# crown-layout.net
KiCad netlist of a schematic drawn in EAGLE
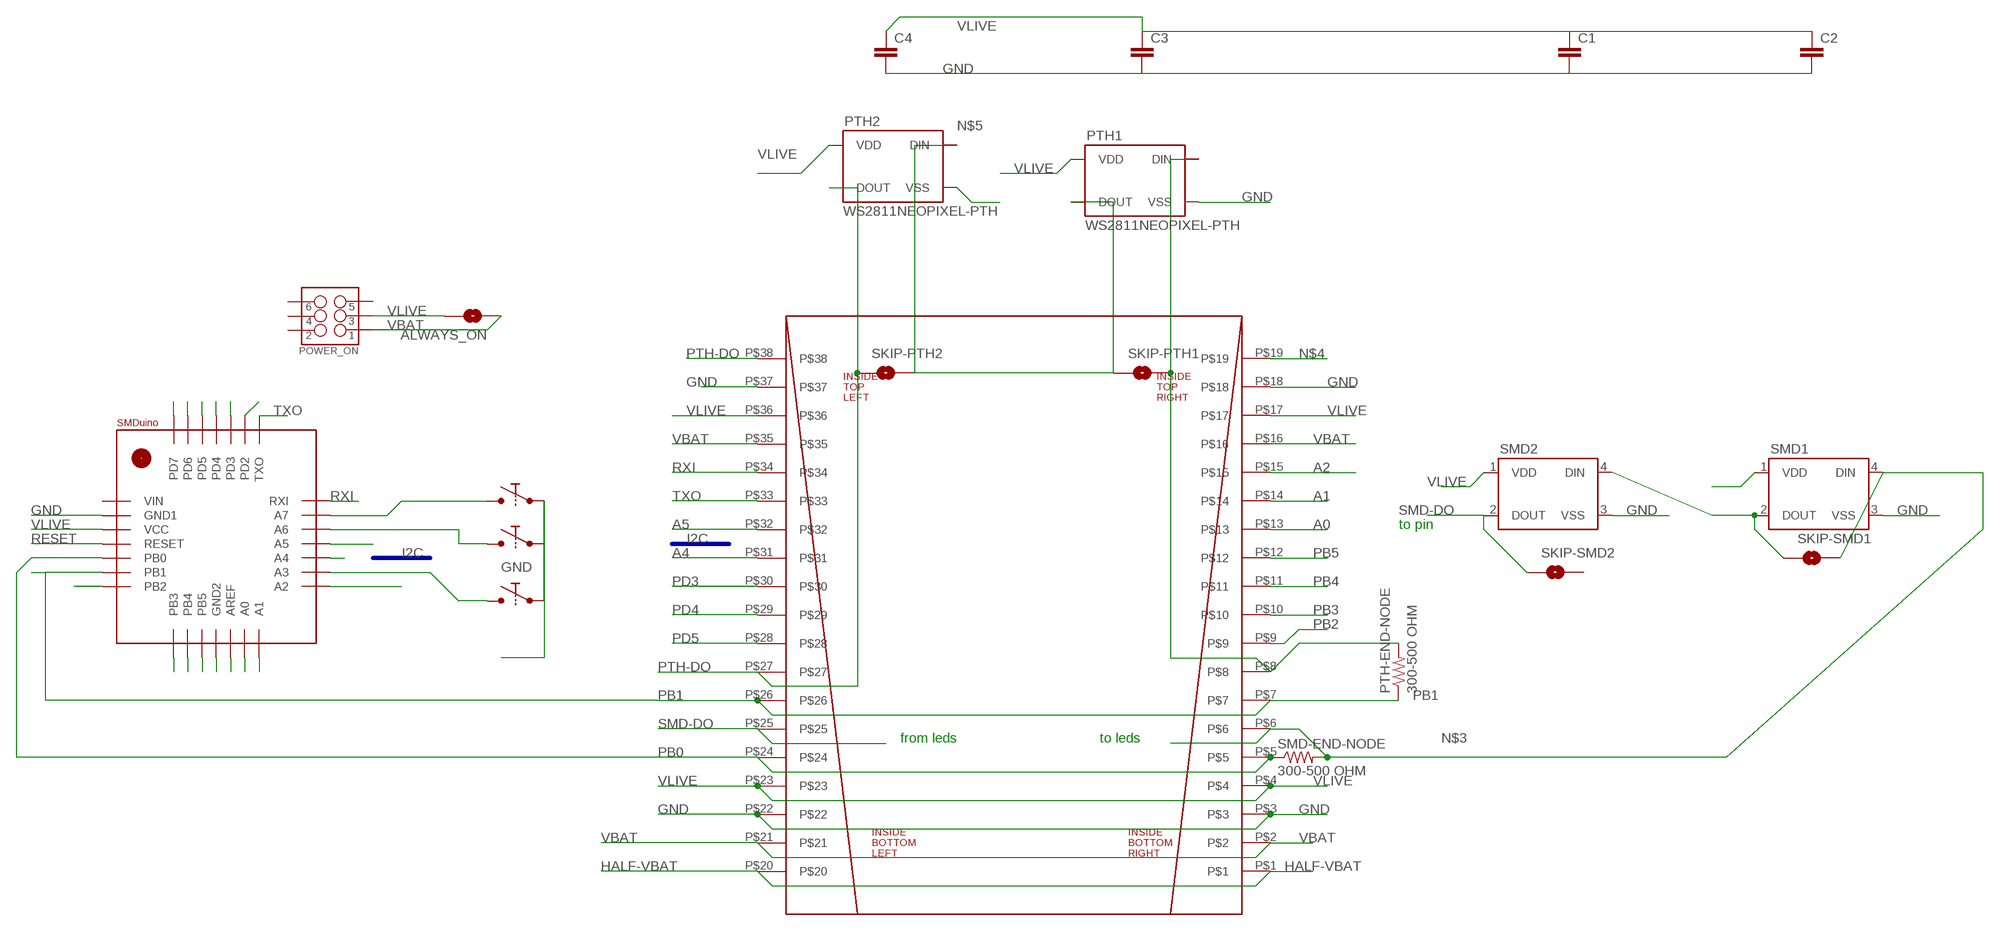
[diagram p0: schematic, sheet 1]

(export (version "E")
  (design (tool "Eeschema 10.0.6"))
  (components
    (comp (ref "A6")
      (value "BUTTONSMD_BUTTON")
      (footprint "eagle-import:SMD_BUTTON")
      (libsource (lib "eagle-import") (part "BUTTONSMD_BUTTON"))
    )
    (comp (ref "A7")
      (value "BUTTONSMD_BUTTON")
      (footprint "eagle-import:SMD_BUTTON")
      (libsource (lib "eagle-import") (part "BUTTONSMD_BUTTON"))
    )
    (comp (ref "ALWAYS_ON")
      (value "SOLDERJUMPERNC2")
      (footprint "eagle-import:SJ_2S-NOTRACE")
      (libsource (lib "eagle-import") (part "SOLDERJUMPERNC2"))
    )
    (comp (ref "C1")
      (value "CAP0805")
      (footprint "eagle-import:0805")
      (libsource (lib "eagle-import") (part "CAP0805"))
    )
    (comp (ref "C2")
      (value "CAP0805")
      (footprint "eagle-import:0805")
      (libsource (lib "eagle-import") (part "CAP0805"))
    )
    (comp (ref "C3")
      (value "CAP0805")
      (footprint "eagle-import:0805")
      (libsource (lib "eagle-import") (part "CAP0805"))
    )
    (comp (ref "C4")
      (value "CAP0805")
      (footprint "eagle-import:0805")
      (libsource (lib "eagle-import") (part "CAP0805"))
    )
    (comp (ref "D2")
      (value "BUTTONSMD_BUTTON")
      (footprint "eagle-import:SMD_BUTTON")
      (libsource (lib "eagle-import") (part "BUTTONSMD_BUTTON"))
    )
    (comp (ref "POWER_ON")
      (value "M03X2FEMALE_SMD")
      (footprint "eagle-import:2X3_SMD")
      (libsource (lib "eagle-import") (part "M03X2FEMALE_SMD"))
    )
    (comp (ref "PTH-END-NODE")
      (value "300-500 OHM")
      (footprint "eagle-import:0805")
      (libsource (lib "eagle-import") (part "RESISTOR0805-RES"))
    )
    (comp (ref "PTH1")
      (value "WS2811NEOPIXEL-PTH")
      (footprint "eagle-import:WS2811-PTH-FLAT")
      (libsource (lib "eagle-import") (part "WS2811NEOPIXEL-PTH"))
    )
    (comp (ref "PTH2")
      (value "WS2811NEOPIXEL-PTH")
      (footprint "eagle-import:WS2811-PTH-FLAT")
      (libsource (lib "eagle-import") (part "WS2811NEOPIXEL-PTH"))
    )
    (comp (ref "SKIP-PTH1")
      (value "SOLDERJUMPERNC2")
      (footprint "eagle-import:SJ_2S-NOTRACE")
      (libsource (lib "eagle-import") (part "SOLDERJUMPERNC2"))
    )
    (comp (ref "SKIP-PTH2")
      (value "SOLDERJUMPERNC2")
      (footprint "eagle-import:SJ_2S-NOTRACE")
      (libsource (lib "eagle-import") (part "SOLDERJUMPERNC2"))
    )
    (comp (ref "SKIP-SMD1")
      (value "SOLDERJUMPERNC2")
      (footprint "eagle-import:SJ_2S-NOTRACE")
      (libsource (lib "eagle-import") (part "SOLDERJUMPERNC2"))
    )
    (comp (ref "SKIP-SMD2")
      (value "SOLDERJUMPERNC2")
      (footprint "eagle-import:SJ_2S-NOTRACE")
      (libsource (lib "eagle-import") (part "SOLDERJUMPERNC2"))
    )
    (comp (ref "SMD-END-NODE")
      (value "300-500 OHM")
      (footprint "eagle-import:0805")
      (libsource (lib "eagle-import") (part "RESISTOR0805-RES"))
    )
    (comp (ref "SMD1")
      (value "WS2812B")
      (footprint "eagle-import:WS2812B")
      (libsource (lib "eagle-import") (part "WS2812B"))
    )
    (comp (ref "SMD2")
      (value "WS2812B")
      (footprint "eagle-import:WS2812B")
      (libsource (lib "eagle-import") (part "WS2812B"))
    )
    (comp (ref "U$1")
      (value "SMDUINO")
      (footprint "eagle-import:SMDUINO")
      (libsource (lib "eagle-import") (part "SMDUINO"))
    )
    (comp (ref "U$2")
      (value "CROWNSTANDARD")
      (footprint "eagle-import:CROWN")
      (libsource (lib "eagle-import") (part "CROWNSTANDARD"))
    )
  )
  (nets
    (net (code "2") (name "/A0") (class "Default")
      (node (ref "U$1") (pin "A0") (pinfunction "A0_A0") (pintype "bidirectional"))
      (node (ref "U$2") (pin "P$13") (pinfunction "P$13_P$13") (pintype "bidirectional"))
    )
    (net (code "3") (name "/A1") (class "Default")
      (node (ref "U$1") (pin "A1") (pinfunction "A1_A1") (pintype "bidirectional"))
      (node (ref "U$2") (pin "P$14") (pinfunction "P$14_P$14") (pintype "bidirectional"))
    )
    (net (code "4") (name "/A2") (class "Default")
      (node (ref "U$1") (pin "A2") (pinfunction "A2_A2") (pintype "bidirectional"))
      (node (ref "U$2") (pin "P$15") (pinfunction "P$15_P$15") (pintype "bidirectional"))
    )
    (net (code "5") (name "/A4") (class "Default")
      (node (ref "U$1") (pin "A4") (pinfunction "A4_A4") (pintype "bidirectional"))
      (node (ref "U$2") (pin "P$31") (pinfunction "P$31_P$31") (pintype "bidirectional"))
    )
    (net (code "6") (name "/A5") (class "Default")
      (node (ref "U$1") (pin "A5") (pinfunction "A5_A5") (pintype "bidirectional"))
      (node (ref "U$2") (pin "P$32") (pinfunction "P$32_P$32") (pintype "bidirectional"))
    )
    (net (code "7") (name "/GND") (class "Default")
      (node (ref "A6") (pin "P$3") (pinfunction "P$2_P$3") (pintype "bidirectional"))
      (node (ref "A6") (pin "P$4") (pinfunction "P$2_P$4") (pintype "bidirectional"))
      (node (ref "A7") (pin "P$3") (pinfunction "P$2_P$3") (pintype "bidirectional"))
      (node (ref "A7") (pin "P$4") (pinfunction "P$2_P$4") (pintype "bidirectional"))
      (node (ref "C1") (pin "2") (pinfunction "2_2") (pintype "passive"))
      (node (ref "C2") (pin "2") (pinfunction "2_2") (pintype "passive"))
      (node (ref "C3") (pin "2") (pinfunction "2_2") (pintype "passive"))
      (node (ref "C4") (pin "2") (pinfunction "2_2") (pintype "passive"))
      (node (ref "D2") (pin "P$3") (pinfunction "P$2_P$3") (pintype "bidirectional"))
      (node (ref "D2") (pin "P$4") (pinfunction "P$2_P$4") (pintype "bidirectional"))
      (node (ref "PTH1") (pin "P$2") (pinfunction "VSS_P$2") (pintype "power_in"))
      (node (ref "PTH1") (pin "P$6") (pinfunction "VSS_P$6") (pintype "power_in"))
      (node (ref "PTH2") (pin "P$2") (pinfunction "VSS_P$2") (pintype "power_in"))
      (node (ref "PTH2") (pin "P$6") (pinfunction "VSS_P$6") (pintype "power_in"))
      (node (ref "SMD1") (pin "3") (pinfunction "VSS_3") (pintype "power_in"))
      (node (ref "SMD2") (pin "3") (pinfunction "VSS_3") (pintype "power_in"))
      (node (ref "U$1") (pin "GND1") (pinfunction "GND1_GND1") (pintype "bidirectional"))
      (node (ref "U$2") (pin "P$18") (pinfunction "P$18_P$18") (pintype "bidirectional"))
      (node (ref "U$2") (pin "P$22") (pinfunction "P$22_P$22") (pintype "bidirectional"))
      (node (ref "U$2") (pin "P$3") (pinfunction "P$3_P$3") (pintype "bidirectional"))
      (node (ref "U$2") (pin "P$37") (pinfunction "P$37_P$37") (pintype "bidirectional"))
    )
    (net (code "8") (name "/HALF-VBAT") (class "Default")
      (node (ref "U$2") (pin "P$1") (pinfunction "P$1_P$1") (pintype "bidirectional"))
      (node (ref "U$2") (pin "P$20") (pinfunction "P$20_P$20") (pintype "bidirectional"))
    )
    (net (code "9") (name "/N$3") (class "Default")
      (node (ref "SKIP-SMD1") (pin "2") (pinfunction "2_2") (pintype "passive"))
      (node (ref "SMD-END-NODE") (pin "2") (pinfunction "2_2") (pintype "passive"))
      (node (ref "SMD1") (pin "4") (pinfunction "DIN_4") (pintype "input"))
      (node (ref "U$2") (pin "P$6") (pinfunction "P$6_P$6") (pintype "bidirectional"))
    )
    (net (code "10") (name "/N$4") (class "Default")
      (node (ref "PTH-END-NODE") (pin "2") (pinfunction "2_2") (pintype "passive"))
      (node (ref "PTH1") (pin "P$4") (pinfunction "DIN_P$4") (pintype "input"))
      (node (ref "PTH1") (pin "P$8") (pinfunction "DIN_P$8") (pintype "input"))
      (node (ref "SKIP-PTH1") (pin "2") (pinfunction "2_2") (pintype "passive"))
      (node (ref "U$2") (pin "P$19") (pinfunction "P$19_P$19") (pintype "bidirectional"))
      (node (ref "U$2") (pin "P$8") (pinfunction "P$8_P$8") (pintype "bidirectional"))
    )
    (net (code "11") (name "/N$5") (class "Default")
      (node (ref "PTH1") (pin "P$1") (pinfunction "DOUT_P$1") (pintype "output"))
      (node (ref "PTH1") (pin "P$5") (pinfunction "DOUT_P$5") (pintype "output"))
      (node (ref "PTH2") (pin "P$4") (pinfunction "DIN_P$4") (pintype "input"))
      (node (ref "PTH2") (pin "P$8") (pinfunction "DIN_P$8") (pintype "input"))
      (node (ref "SKIP-PTH1") (pin "1") (pinfunction "1_1") (pintype "passive"))
      (node (ref "SKIP-PTH2") (pin "2") (pinfunction "2_2") (pintype "passive"))
    )
    (net (code "12") (name "/PB0") (class "Default")
      (node (ref "SMD-END-NODE") (pin "1") (pinfunction "1_1") (pintype "passive"))
      (node (ref "U$1") (pin "PB0") (pinfunction "PB0_PB0") (pintype "bidirectional"))
      (node (ref "U$2") (pin "P$24") (pinfunction "P$24_P$24") (pintype "bidirectional"))
      (node (ref "U$2") (pin "P$5") (pinfunction "P$5_P$5") (pintype "bidirectional"))
    )
    (net (code "13") (name "/PB1") (class "Default")
      (node (ref "PTH-END-NODE") (pin "1") (pinfunction "1_1") (pintype "passive"))
      (node (ref "U$1") (pin "PB1") (pinfunction "PB1_PB1") (pintype "bidirectional"))
      (node (ref "U$2") (pin "P$26") (pinfunction "P$26_P$26") (pintype "bidirectional"))
      (node (ref "U$2") (pin "P$7") (pinfunction "P$7_P$7") (pintype "bidirectional"))
    )
    (net (code "14") (name "/PB2") (class "Default")
      (node (ref "U$1") (pin "PB2") (pinfunction "PB2_PB2") (pintype "bidirectional"))
      (node (ref "U$2") (pin "P$9") (pinfunction "P$9_P$9") (pintype "bidirectional"))
    )
    (net (code "15") (name "/PB3") (class "Default")
      (node (ref "U$1") (pin "PB3") (pinfunction "PB3_PB3") (pintype "bidirectional"))
      (node (ref "U$2") (pin "P$10") (pinfunction "P$10_P$10") (pintype "bidirectional"))
    )
    (net (code "16") (name "/PB4") (class "Default")
      (node (ref "U$1") (pin "PB4") (pinfunction "PB4_PB4") (pintype "bidirectional"))
      (node (ref "U$2") (pin "P$11") (pinfunction "P$11_P$11") (pintype "bidirectional"))
    )
    (net (code "17") (name "/PB5") (class "Default")
      (node (ref "U$2") (pin "P$12") (pinfunction "P$12_P$12") (pintype "bidirectional"))
    )
    (net (code "18") (name "/PD3") (class "Default")
      (node (ref "U$1") (pin "PD3") (pinfunction "PD3_PD3") (pintype "bidirectional"))
      (node (ref "U$2") (pin "P$30") (pinfunction "P$30_P$30") (pintype "bidirectional"))
    )
    (net (code "19") (name "/PD4") (class "Default")
      (node (ref "U$1") (pin "PD4") (pinfunction "PD4_PD4") (pintype "bidirectional"))
      (node (ref "U$2") (pin "P$29") (pinfunction "P$29_P$29") (pintype "bidirectional"))
    )
    (net (code "20") (name "/PD5") (class "Default")
      (node (ref "U$1") (pin "PD5") (pinfunction "PD5_PD5") (pintype "bidirectional"))
      (node (ref "U$2") (pin "P$28") (pinfunction "P$28_P$28") (pintype "bidirectional"))
    )
    (net (code "21") (name "/PTH-DO") (class "Default")
      (node (ref "PTH2") (pin "P$1") (pinfunction "DOUT_P$1") (pintype "output"))
      (node (ref "PTH2") (pin "P$5") (pinfunction "DOUT_P$5") (pintype "output"))
      (node (ref "SKIP-PTH2") (pin "1") (pinfunction "1_1") (pintype "passive"))
      (node (ref "U$2") (pin "P$27") (pinfunction "P$27_P$27") (pintype "bidirectional"))
      (node (ref "U$2") (pin "P$38") (pinfunction "P$38_P$38") (pintype "bidirectional"))
    )
    (net (code "22") (name "/RESET") (class "Default")
      (node (ref "U$1") (pin "RESET") (pinfunction "RESET_RESET") (pintype "bidirectional"))
    )
    (net (code "23") (name "/RXI") (class "Default")
      (node (ref "U$1") (pin "RXI") (pinfunction "RXI_RXI") (pintype "bidirectional"))
      (node (ref "U$2") (pin "P$34") (pinfunction "P$34_P$34") (pintype "bidirectional"))
    )
    (net (code "24") (name "/SMD-DO") (class "Default")
      (node (ref "SKIP-SMD2") (pin "1") (pinfunction "1_1") (pintype "passive"))
      (node (ref "SMD2") (pin "2") (pinfunction "DOUT_2") (pintype "output"))
      (node (ref "U$2") (pin "P$25") (pinfunction "P$25_P$25") (pintype "bidirectional"))
    )
    (net (code "25") (name "/TXO") (class "Default")
      (node (ref "U$1") (pin "TXO") (pinfunction "TXO_TXO") (pintype "bidirectional"))
      (node (ref "U$2") (pin "P$33") (pinfunction "P$33_P$33") (pintype "bidirectional"))
    )
    (net (code "26") (name "/VBAT") (class "Default")
      (node (ref "ALWAYS_ON") (pin "1") (pinfunction "1_1") (pintype "passive"))
      (node (ref "POWER_ON") (pin "1") (pinfunction "1_1") (pintype "bidirectional"))
      (node (ref "U$2") (pin "P$16") (pinfunction "P$16_P$16") (pintype "bidirectional"))
      (node (ref "U$2") (pin "P$2") (pinfunction "P$2_P$2") (pintype "bidirectional"))
      (node (ref "U$2") (pin "P$21") (pinfunction "P$21_P$21") (pintype "bidirectional"))
      (node (ref "U$2") (pin "P$35") (pinfunction "P$35_P$35") (pintype "bidirectional"))
    )
    (net (code "27") (name "/VLIVE") (class "Default")
      (node (ref "ALWAYS_ON") (pin "2") (pinfunction "2_2") (pintype "passive"))
      (node (ref "C1") (pin "1") (pinfunction "1_1") (pintype "passive"))
      (node (ref "C2") (pin "1") (pinfunction "1_1") (pintype "passive"))
      (node (ref "C3") (pin "1") (pinfunction "1_1") (pintype "passive"))
      (node (ref "C4") (pin "1") (pinfunction "1_1") (pintype "passive"))
      (node (ref "POWER_ON") (pin "3") (pinfunction "3_3") (pintype "bidirectional"))
      (node (ref "PTH1") (pin "P$3") (pinfunction "VDD_P$3") (pintype "power_in"))
      (node (ref "PTH1") (pin "P$7") (pinfunction "VDD_P$7") (pintype "power_in"))
      (node (ref "PTH2") (pin "P$3") (pinfunction "VDD_P$3") (pintype "power_in"))
      (node (ref "PTH2") (pin "P$7") (pinfunction "VDD_P$7") (pintype "power_in"))
      (node (ref "SMD1") (pin "1") (pinfunction "VDD_1") (pintype "power_in"))
      (node (ref "SMD2") (pin "1") (pinfunction "VDD_1") (pintype "power_in"))
      (node (ref "U$1") (pin "VCC") (pinfunction "VCC_VCC") (pintype "bidirectional"))
      (node (ref "U$2") (pin "P$17") (pinfunction "P$17_P$17") (pintype "bidirectional"))
      (node (ref "U$2") (pin "P$23") (pinfunction "P$23_P$23") (pintype "bidirectional"))
      (node (ref "U$2") (pin "P$36") (pinfunction "P$36_P$36") (pintype "bidirectional"))
      (node (ref "U$2") (pin "P$4") (pinfunction "P$4_P$4") (pintype "bidirectional"))
    )
    (net (code "29") (name "Net-(A6-P$1-PadP$2)") (class "Default")
      (node (ref "A6") (pin "P$1") (pinfunction "P$1_P$1") (pintype "bidirectional"))
      (node (ref "A6") (pin "P$2") (pinfunction "P$1_P$2") (pintype "bidirectional"))
      (node (ref "U$1") (pin "A3") (pinfunction "A3_A3") (pintype "bidirectional"))
    )
    (net (code "30") (name "Net-(A7-P$1-PadP$2)") (class "Default")
      (node (ref "A7") (pin "P$1") (pinfunction "P$1_P$1") (pintype "bidirectional"))
      (node (ref "A7") (pin "P$2") (pinfunction "P$1_P$2") (pintype "bidirectional"))
      (node (ref "U$1") (pin "A6") (pinfunction "A6_A6") (pintype "bidirectional"))
    )
    (net (code "31") (name "Net-(D2-P$1-PadP$2)") (class "Default")
      (node (ref "D2") (pin "P$1") (pinfunction "P$1_P$1") (pintype "bidirectional"))
      (node (ref "D2") (pin "P$2") (pinfunction "P$1_P$2") (pintype "bidirectional"))
      (node (ref "U$1") (pin "A7") (pinfunction "A7_A7") (pintype "bidirectional"))
    )
    (net (code "32") (name "Net-(SMD1-DOUT)") (class "Default")
      (node (ref "SKIP-SMD1") (pin "1") (pinfunction "1_1") (pintype "passive"))
      (node (ref "SMD1") (pin "2") (pinfunction "DOUT_2") (pintype "output"))
      (node (ref "SMD2") (pin "4") (pinfunction "DIN_4") (pintype "input"))
    )
    (net (code "33") (name "unconnected-(POWER_ON-Pad2)") (class "Default")
      (node (ref "POWER_ON") (pin "2") (pinfunction "2_2") (pintype "bidirectional"))
    )
    (net (code "34") (name "unconnected-(POWER_ON-Pad4)") (class "Default")
      (node (ref "POWER_ON") (pin "4") (pinfunction "4_4") (pintype "bidirectional"))
    )
    (net (code "35") (name "unconnected-(POWER_ON-Pad5)") (class "Default")
      (node (ref "POWER_ON") (pin "5") (pinfunction "5_5") (pintype "bidirectional"))
    )
    (net (code "36") (name "unconnected-(POWER_ON-Pad6)") (class "Default")
      (node (ref "POWER_ON") (pin "6") (pinfunction "6_6") (pintype "bidirectional"))
    )
    (net (code "37") (name "unconnected-(SKIP-SMD2-Pad2)") (class "Default")
      (node (ref "SKIP-SMD2") (pin "2") (pinfunction "2_2") (pintype "passive"))
    )
    (net (code "38") (name "unconnected-(U$1-PadAREF)") (class "Default")
      (node (ref "U$1") (pin "AREF") (pinfunction "AREF_AREF") (pintype "bidirectional"))
    )
    (net (code "39") (name "unconnected-(U$1-PadGND2)") (class "Default")
      (node (ref "U$1") (pin "GND2") (pinfunction "GND2_GND2") (pintype "bidirectional"))
    )
    (net (code "40") (name "unconnected-(U$1-PadPB5)") (class "Default")
      (node (ref "U$1") (pin "PB5") (pinfunction "PB5_PB5") (pintype "bidirectional"))
    )
    (net (code "41") (name "unconnected-(U$1-PadPD2)") (class "Default")
      (node (ref "U$1") (pin "PD2") (pinfunction "PD2_PD2") (pintype "bidirectional"))
    )
    (net (code "42") (name "unconnected-(U$1-PadPD6)") (class "Default")
      (node (ref "U$1") (pin "PD6") (pinfunction "PD6_PD6") (pintype "bidirectional"))
    )
    (net (code "43") (name "unconnected-(U$1-PadPD7)") (class "Default")
      (node (ref "U$1") (pin "PD7") (pinfunction "PD7_PD7") (pintype "bidirectional"))
    )
    (net (code "44") (name "unconnected-(U$1-PadVIN)") (class "Default")
      (node (ref "U$1") (pin "VIN") (pinfunction "VIN_VIN") (pintype "bidirectional"))
    )
  )
)
